# radio_fm.net
KiCad netlist of a schematic drawn in EAGLE
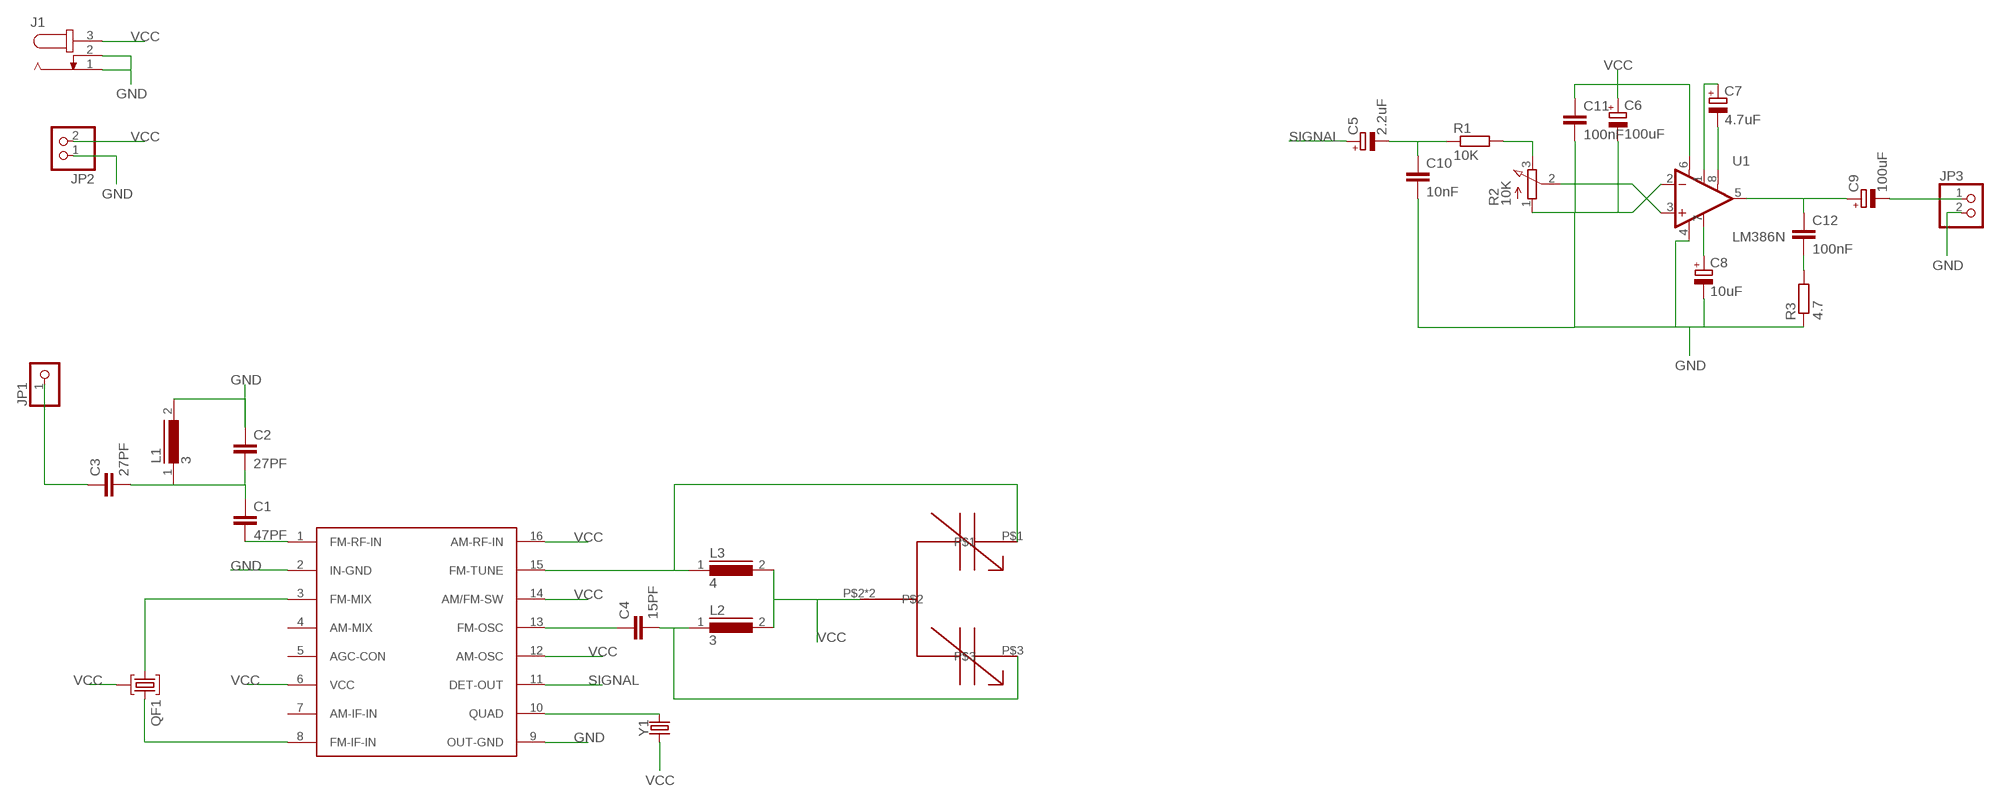
[diagram p0: schematic, sheet 1]

(export (version "E")
  (design (tool "Eeschema 10.0.6"))
  (components
    (comp (ref "C1")
      (value "47PF")
      (footprint "eagle-import:C025-040X050")
      (libsource (lib "eagle-import") (part "C-EU025-040X050"))
    )
    (comp (ref "C2")
      (value "27PF")
      (footprint "eagle-import:C025-040X050")
      (libsource (lib "eagle-import") (part "C-EU025-040X050"))
    )
    (comp (ref "C3")
      (value "27PF")
      (footprint "eagle-import:C025-040X050")
      (libsource (lib "eagle-import") (part "C-EU025-040X050"))
    )
    (comp (ref "C4")
      (value "15PF")
      (footprint "eagle-import:C025-040X050")
      (libsource (lib "eagle-import") (part "C-EU025-040X050"))
    )
    (comp (ref "C5")
      (value "2.2uF")
      (footprint "eagle-import:E2,5-6E")
      (libsource (lib "eagle-import") (part "CPOL-EUE2,5-6E"))
    )
    (comp (ref "C6")
      (value "100uF")
      (footprint "eagle-import:E2,5-6E")
      (libsource (lib "eagle-import") (part "CPOL-EUE2,5-6E"))
    )
    (comp (ref "C7")
      (value "4.7uF")
      (footprint "eagle-import:E2,5-6E")
      (libsource (lib "eagle-import") (part "CPOL-EUE2,5-6E"))
    )
    (comp (ref "C8")
      (value "10uF")
      (footprint "eagle-import:E2,5-6E")
      (libsource (lib "eagle-import") (part "CPOL-EUE2,5-6E"))
    )
    (comp (ref "C9")
      (value "100uF")
      (footprint "eagle-import:E2,5-6E")
      (libsource (lib "eagle-import") (part "CPOL-EUE2,5-6E"))
    )
    (comp (ref "C10")
      (value "10nF")
      (footprint "eagle-import:C050-030X075")
      (libsource (lib "eagle-import") (part "C-EU050-030X075"))
    )
    (comp (ref "C11")
      (value "100nF")
      (footprint "eagle-import:C050-030X075")
      (libsource (lib "eagle-import") (part "C-EU050-030X075"))
    )
    (comp (ref "C12")
      (value "100nF")
      (footprint "eagle-import:C050-030X075")
      (libsource (lib "eagle-import") (part "C-EU050-030X075"))
    )
    (comp (ref "J1")
      (value "JACK-PLUG0")
      (footprint "eagle-import:SPC4077")
      (libsource (lib "eagle-import") (part "JACK-PLUG0"))
    )
    (comp (ref "JP1")
      (value "PINHD-1X1")
      (footprint "eagle-import:1X01")
      (libsource (lib "eagle-import") (part "PINHD-1X1"))
    )
    (comp (ref "JP2")
      (value "PINHD-1X2")
      (footprint "eagle-import:1X02")
      (libsource (lib "eagle-import") (part "PINHD-1X2"))
    )
    (comp (ref "JP3")
      (value "PINHD-1X2")
      (footprint "eagle-import:1X02")
      (libsource (lib "eagle-import") (part "PINHD-1X2"))
    )
    (comp (ref "L1")
      (value "3")
      (footprint "eagle-import:82114R")
      (libsource (lib "eagle-import") (part "82114R"))
    )
    (comp (ref "L2")
      (value "3")
      (footprint "eagle-import:82114R")
      (libsource (lib "eagle-import") (part "82114R"))
    )
    (comp (ref "L3")
      (value "4")
      (footprint "eagle-import:82114R")
      (libsource (lib "eagle-import") (part "82114R"))
    )
    (comp (ref "QF1")
      (value "10M7AHC49T")
      (footprint "eagle-import:HC49U")
      (libsource (lib "eagle-import") (part "10MAHC49T7"))
    )
    (comp (ref "R1")
      (value "10K")
      (footprint "eagle-import:0207_7")
      (libsource (lib "eagle-import") (part "R-EU_0207/7"))
    )
    (comp (ref "R2")
      (value "10K")
      (footprint "eagle-import:3RP_1610N")
      (libsource (lib "eagle-import") (part "3RP/1610N"))
    )
    (comp (ref "R3")
      (value "4.7")
      (footprint "eagle-import:0207_7")
      (libsource (lib "eagle-import") (part "R-EU_0207/7"))
    )
    (comp (ref "U$1")
      (value "TA2003")
      (footprint "eagle-import:DIL16")
      (libsource (lib "eagle-import") (part "TA2003"))
    )
    (comp (ref "U$2")
      (value "VARCO_KEMATIAN_V2")
      (footprint "eagle-import:VARCO_KEMATIAN2")
      (libsource (lib "eagle-import") (part "VARCO_KEMATIAN_V2"))
    )
    (comp (ref "U1")
      (value "LM386N")
      (footprint "eagle-import:DIP08")
      (libsource (lib "eagle-import") (part "LM386"))
    )
    (comp (ref "Y1")
      (value "CRYSTALPTH-HC49US")
      (footprint "eagle-import:HC49US")
      (libsource (lib "eagle-import") (part "CRYSTALPTH-HC49US"))
    )
  )
  (nets
    (net (code "1") (name "/GND") (class "Default")
      (node (ref "C10") (pin "2") (pinfunction "2_2") (pintype "passive"))
      (node (ref "C11") (pin "2") (pinfunction "2_2") (pintype "passive"))
      (node (ref "C2") (pin "1") (pinfunction "1_1") (pintype "passive"))
      (node (ref "C6") (pin "-") (pinfunction "-_-") (pintype "passive"))
      (node (ref "C8") (pin "-") (pinfunction "-_-") (pintype "passive"))
      (node (ref "J1") (pin "1") (pinfunction "1_1") (pintype "passive"))
      (node (ref "J1") (pin "2") (pinfunction "2_2") (pintype "passive"))
      (node (ref "JP2") (pin "1") (pinfunction "1_1") (pintype "passive"))
      (node (ref "JP3") (pin "2") (pinfunction "2_2") (pintype "passive"))
      (node (ref "L1") (pin "2") (pinfunction "2_2") (pintype "passive"))
      (node (ref "R2") (pin "1") (pinfunction "A_1") (pintype "passive"))
      (node (ref "R3") (pin "1") (pinfunction "1_1") (pintype "passive"))
      (node (ref "U$1") (pin "2") (pinfunction "IN-GND_2") (pintype "bidirectional"))
      (node (ref "U$1") (pin "9") (pinfunction "OUT-GND_9") (pintype "bidirectional"))
      (node (ref "U1") (pin "2") (pinfunction "-IN_2") (pintype "input"))
      (node (ref "U1") (pin "4") (pinfunction "V-_4") (pintype "power_in"))
    )
    (net (code "2") (name "/SIGNAL") (class "Default")
      (node (ref "C5") (pin "+") (pinfunction "+_+") (pintype "passive"))
      (node (ref "U$1") (pin "11") (pinfunction "DET-OUT_11") (pintype "bidirectional"))
    )
    (net (code "3") (name "/VCC") (class "Default")
      (node (ref "C11") (pin "1") (pinfunction "1_1") (pintype "passive"))
      (node (ref "C6") (pin "+") (pinfunction "+_+") (pintype "passive"))
      (node (ref "J1") (pin "3") (pinfunction "3_3") (pintype "passive"))
      (node (ref "JP2") (pin "2") (pinfunction "2_2") (pintype "passive"))
      (node (ref "L2") (pin "2") (pinfunction "2_2") (pintype "passive"))
      (node (ref "L3") (pin "2") (pinfunction "2_2") (pintype "passive"))
      (node (ref "QF1") (pin "2") (pinfunction "2_2") (pintype "passive"))
      (node (ref "U$1") (pin "12") (pinfunction "AM-OSC_12") (pintype "bidirectional"))
      (node (ref "U$1") (pin "14") (pinfunction "AM/FM-SW_14") (pintype "bidirectional"))
      (node (ref "U$1") (pin "16") (pinfunction "AM-RF-IN_16") (pintype "bidirectional"))
      (node (ref "U$1") (pin "6") (pinfunction "VCC_6") (pintype "bidirectional"))
      (node (ref "U$2") (pin "P$2") (pinfunction "P$2_P$2") (pintype "bidirectional"))
      (node (ref "U$2") (pin "P$4") (pinfunction "P$2_P$4") (pintype "bidirectional"))
      (node (ref "U1") (pin "6") (pinfunction "V+_6") (pintype "power_in"))
      (node (ref "Y1") (pin "1") (pinfunction "1_1") (pintype "passive"))
    )
    (net (code "4") (name "Net-(C1-Pad1)") (class "Default")
      (node (ref "C1") (pin "1") (pinfunction "1_1") (pintype "passive"))
      (node (ref "C2") (pin "2") (pinfunction "2_2") (pintype "passive"))
      (node (ref "C3") (pin "2") (pinfunction "2_2") (pintype "passive"))
      (node (ref "L1") (pin "1") (pinfunction "1_1") (pintype "passive"))
    )
    (net (code "5") (name "Net-(C3-Pad1)") (class "Default")
      (node (ref "C3") (pin "1") (pinfunction "1_1") (pintype "passive"))
      (node (ref "JP1") (pin "1") (pinfunction "1_1") (pintype "passive"))
    )
    (net (code "6") (name "Net-(C4-Pad2)") (class "Default")
      (node (ref "C4") (pin "2") (pinfunction "2_2") (pintype "passive"))
      (node (ref "L2") (pin "1") (pinfunction "1_1") (pintype "passive"))
      (node (ref "U$2") (pin "P$3") (pinfunction "P$3_P$3") (pintype "bidirectional"))
    )
    (net (code "7") (name "Net-(C7-Pad+)") (class "Default")
      (node (ref "C7") (pin "+") (pinfunction "+_+") (pintype "passive"))
      (node (ref "U1") (pin "1") (pinfunction "GAIN_1") (pintype "bidirectional"))
    )
    (net (code "8") (name "Net-(C7-Pad-)") (class "Default")
      (node (ref "C7") (pin "-") (pinfunction "-_-") (pintype "passive"))
      (node (ref "U1") (pin "8") (pinfunction "GAIN_8") (pintype "bidirectional"))
    )
    (net (code "9") (name "Net-(C9-Pad-)") (class "Default")
      (node (ref "C9") (pin "-") (pinfunction "-_-") (pintype "passive"))
      (node (ref "JP3") (pin "1") (pinfunction "1_1") (pintype "passive"))
    )
    (net (code "10") (name "Net-(C10-Pad1)") (class "Default")
      (node (ref "C10") (pin "1") (pinfunction "1_1") (pintype "passive"))
      (node (ref "C5") (pin "-") (pinfunction "-_-") (pintype "passive"))
      (node (ref "R1") (pin "1") (pinfunction "1_1") (pintype "passive"))
    )
    (net (code "11") (name "Net-(C12-Pad2)") (class "Default")
      (node (ref "C12") (pin "2") (pinfunction "2_2") (pintype "passive"))
      (node (ref "R3") (pin "2") (pinfunction "2_2") (pintype "passive"))
    )
    (net (code "12") (name "Net-(R2-E)") (class "Default")
      (node (ref "R1") (pin "2") (pinfunction "2_2") (pintype "passive"))
      (node (ref "R2") (pin "3") (pinfunction "E_3") (pintype "passive"))
    )
    (net (code "13") (name "Net-(R2-S)") (class "Default")
      (node (ref "R2") (pin "2") (pinfunction "S_2") (pintype "passive"))
      (node (ref "U1") (pin "3") (pinfunction "+IN_3") (pintype "input"))
    )
    (net (code "14") (name "Net-(U$1-FM-IF-IN)") (class "Default")
      (node (ref "QF1") (pin "3") (pinfunction "3_3") (pintype "passive"))
      (node (ref "U$1") (pin "8") (pinfunction "FM-IF-IN_8") (pintype "bidirectional"))
    )
    (net (code "15") (name "Net-(U$1-FM-MIX)") (class "Default")
      (node (ref "QF1") (pin "1") (pinfunction "1_1") (pintype "passive"))
      (node (ref "U$1") (pin "3") (pinfunction "FM-MIX_3") (pintype "bidirectional"))
    )
    (net (code "16") (name "Net-(U$1-FM-OSC)") (class "Default")
      (node (ref "C4") (pin "1") (pinfunction "1_1") (pintype "passive"))
      (node (ref "U$1") (pin "13") (pinfunction "FM-OSC_13") (pintype "bidirectional"))
    )
    (net (code "17") (name "Net-(U$1-FM-RF-IN)") (class "Default")
      (node (ref "C1") (pin "2") (pinfunction "2_2") (pintype "passive"))
      (node (ref "U$1") (pin "1") (pinfunction "FM-RF-IN_1") (pintype "bidirectional"))
    )
    (net (code "18") (name "Net-(U$1-FM-TUNE)") (class "Default")
      (node (ref "L3") (pin "1") (pinfunction "1_1") (pintype "passive"))
      (node (ref "U$1") (pin "15") (pinfunction "FM-TUNE_15") (pintype "bidirectional"))
      (node (ref "U$2") (pin "P$1") (pinfunction "P$1_P$1") (pintype "bidirectional"))
    )
    (net (code "19") (name "Net-(U$1-QUAD)") (class "Default")
      (node (ref "U$1") (pin "10") (pinfunction "QUAD_10") (pintype "bidirectional"))
      (node (ref "Y1") (pin "2") (pinfunction "2_2") (pintype "passive"))
    )
    (net (code "20") (name "Net-(U1-BP)") (class "Default")
      (node (ref "C8") (pin "+") (pinfunction "+_+") (pintype "passive"))
      (node (ref "U1") (pin "7") (pinfunction "BP_7") (pintype "bidirectional"))
    )
    (net (code "21") (name "Net-(U1-OUT)") (class "Default")
      (node (ref "C12") (pin "1") (pinfunction "1_1") (pintype "passive"))
      (node (ref "C9") (pin "+") (pinfunction "+_+") (pintype "passive"))
      (node (ref "U1") (pin "5") (pinfunction "OUT_5") (pintype "output"))
    )
    (net (code "22") (name "unconnected-(U$1-AGC-CON-Pad5)") (class "Default")
      (node (ref "U$1") (pin "5") (pinfunction "AGC-CON_5") (pintype "bidirectional"))
    )
    (net (code "23") (name "unconnected-(U$1-AM-IF-IN-Pad7)") (class "Default")
      (node (ref "U$1") (pin "7") (pinfunction "AM-IF-IN_7") (pintype "bidirectional"))
    )
    (net (code "24") (name "unconnected-(U$1-AM-MIX-Pad4)") (class "Default")
      (node (ref "U$1") (pin "4") (pinfunction "AM-MIX_4") (pintype "bidirectional"))
    )
  )
)
